# Steering_IOSch.net
KiCad netlist of a schematic drawn in Altium Designer
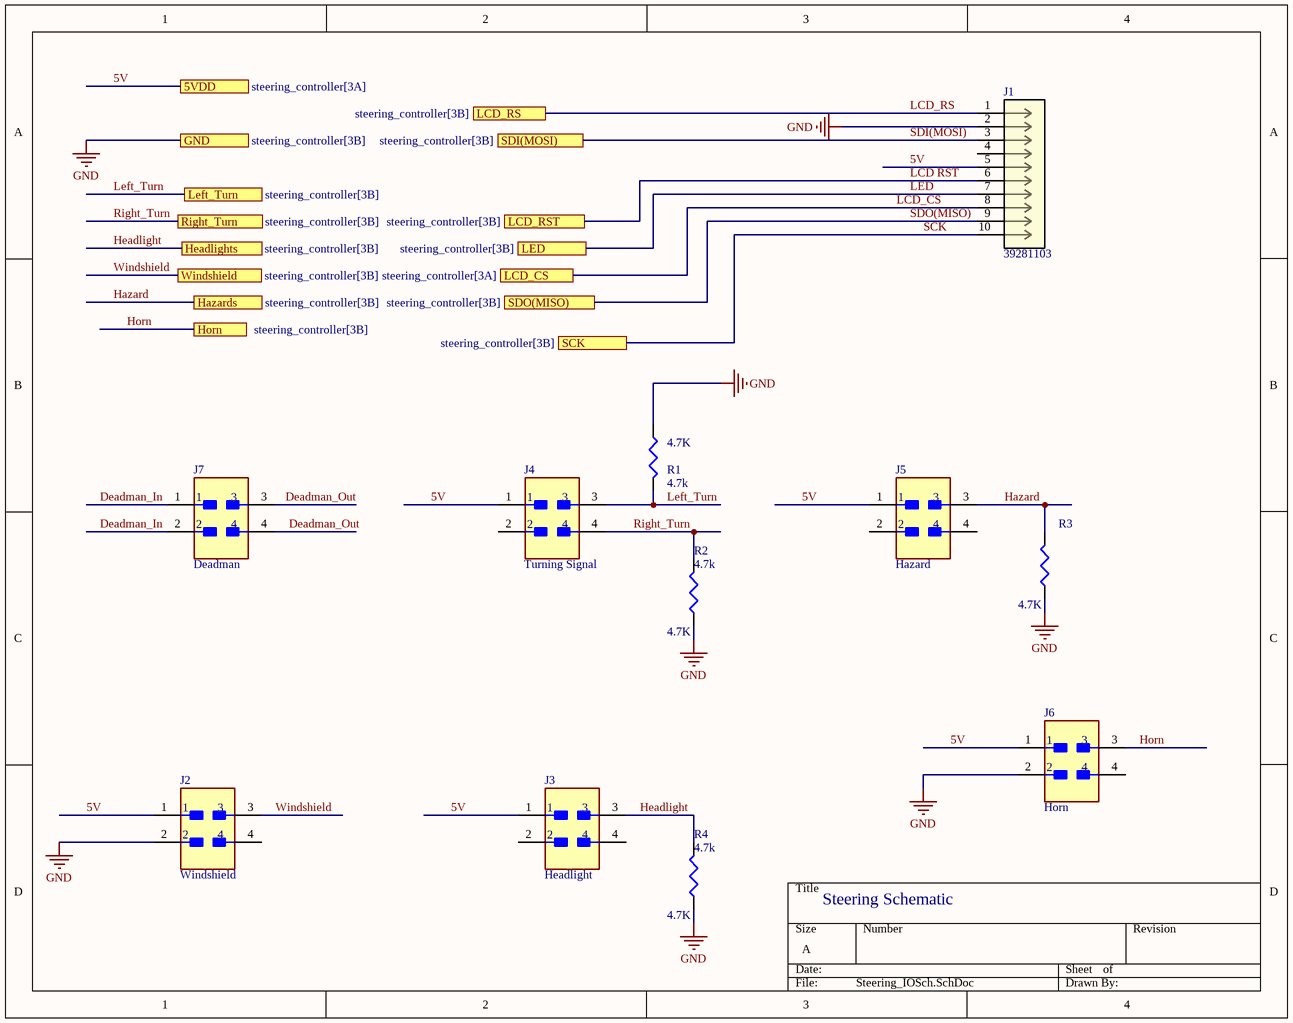
[diagram p0: Steering_IOSch.SchDoc]

(export (version "E")
  (design (tool "Eeschema 10.0.6"))
  (components
    (comp (ref "J1")
      (value "39281103")
      (footprint "CON_39281103")
      (description "No Description Available")
      (libsource (lib "asib") (part "39281103"))
    )
    (comp (ref "J2")
      (value "Windshield")
      (footprint "asib:FP-0039281043-MFG")
      (description "CONN HEADER VERT 4POS 4.2MM. 0039281043")
      (fields (field (name "MANUFACTURER PART NUMBER") "0039281043") (field (name "MANUFACTURER") "Molex"))
      (libsource (lib "asib") (part "1x4_FEMALE_POWER"))
    )
    (comp (ref "J3")
      (value "Headlight")
      (footprint "asib:FP-0039281043-MFG")
      (description "CONN HEADER VERT 4POS 4.2MM. 0039281043")
      (fields (field (name "MANUFACTURER PART NUMBER") "0039281043") (field (name "MANUFACTURER") "Molex"))
      (libsource (lib "asib") (part "1x4_FEMALE_POWER"))
    )
    (comp (ref "J4")
      (value "Turning Signal")
      (footprint "asib:FP-0039281043-MFG")
      (description "CONN HEADER VERT 4POS 4.2MM. 0039281043")
      (fields (field (name "MANUFACTURER PART NUMBER") "0039281043") (field (name "MANUFACTURER") "Molex"))
      (libsource (lib "asib") (part "1x4_FEMALE_POWER"))
    )
    (comp (ref "J5")
      (value "Hazard")
      (footprint "asib:FP-0039281043-MFG")
      (description "CONN HEADER VERT 4POS 4.2MM. 0039281043")
      (fields (field (name "MANUFACTURER PART NUMBER") "0039281043") (field (name "MANUFACTURER") "Molex"))
      (libsource (lib "asib") (part "1x4_FEMALE_POWER"))
    )
    (comp (ref "J6")
      (value "Horn")
      (footprint "asib:FP-0039281043-MFG")
      (description "CONN HEADER VERT 4POS 4.2MM. 0039281043")
      (fields (field (name "MANUFACTURER PART NUMBER") "0039281043") (field (name "MANUFACTURER") "Molex"))
      (libsource (lib "asib") (part "1x4_FEMALE_POWER"))
    )
    (comp (ref "J7")
      (value "Deadman")
      (footprint "asib:FP-0039281043-MFG")
      (description "CONN HEADER VERT 4POS 4.2MM. 0039281043")
      (fields (field (name "MANUFACTURER PART NUMBER") "0039281043") (field (name "MANUFACTURER") "Molex"))
      (libsource (lib "asib") (part "1x4_FEMALE_POWER"))
    )
    (comp (ref "R1")
      (value "4.7k")
      (footprint "0603r")
      (description "SMD Resistor")
      (fields (field (name "ALTIUM_VALUE") "4.7K") (field (name "PUBLISHER") "Altium Limited"))
      (libsource (lib "asib") (part "Res3"))
    )
    (comp (ref "R2")
      (value "4.7k")
      (footprint "0603r")
      (description "SMD Resistor")
      (fields (field (name "ALTIUM_VALUE") "4.7K") (field (name "PUBLISHER") "Altium Limited"))
      (libsource (lib "asib") (part "Res3"))
    )
    (comp (ref "R3")
      (value "4.7K")
      (footprint "0603r")
      (description "SMD Resistor")
      (fields (field (name "PUBLISHER") "Altium Limited"))
      (libsource (lib "asib") (part "Res3"))
    )
    (comp (ref "R4")
      (value "4.7k")
      (footprint "0603r")
      (description "SMD Resistor")
      (fields (field (name "ALTIUM_VALUE") "4.7K") (field (name "PUBLISHER") "Altium Limited"))
      (libsource (lib "asib") (part "Res3"))
    )
  )
  (nets
    (net (code "1") (name "/5V") (class "Default")
      (node (ref "J1") (pin "5") (pinfunction "5_5") (pintype "passive"))
      (node (ref "J2") (pin "1") (pinfunction "1_1") (pintype "passive"))
      (node (ref "J3") (pin "1") (pinfunction "1_1") (pintype "passive"))
      (node (ref "J4") (pin "1") (pinfunction "1_1") (pintype "passive"))
      (node (ref "J5") (pin "1") (pinfunction "1_1") (pintype "passive"))
      (node (ref "J6") (pin "1") (pinfunction "1_1") (pintype "passive"))
    )
    (net (code "2") (name "/Deadman_In") (class "Default")
      (node (ref "J7") (pin "1") (pinfunction "1_1") (pintype "passive"))
      (node (ref "J7") (pin "2") (pinfunction "2_2") (pintype "passive"))
    )
    (net (code "3") (name "/Deadman_Out") (class "Default")
      (node (ref "J7") (pin "3") (pinfunction "3_3") (pintype "passive"))
      (node (ref "J7") (pin "4") (pinfunction "4_4") (pintype "passive"))
    )
    (net (code "4") (name "/Hazard") (class "Default")
      (node (ref "J5") (pin "3") (pinfunction "3_3") (pintype "passive"))
      (node (ref "R3") (pin "2") (pinfunction "2_2") (pintype "passive"))
    )
    (net (code "5") (name "/Headlight") (class "Default")
      (node (ref "J3") (pin "3") (pinfunction "3_3") (pintype "passive"))
      (node (ref "R4") (pin "2") (pinfunction "2_2") (pintype "passive"))
    )
    (net (code "6") (name "/Horn") (class "Default")
      (node (ref "J6") (pin "3") (pinfunction "3_3") (pintype "passive"))
    )
    (net (code "7") (name "/LCD RST") (class "Default")
      (node (ref "J1") (pin "6") (pinfunction "6_6") (pintype "passive"))
    )
    (net (code "8") (name "/LCD_CS") (class "Default")
      (node (ref "J1") (pin "8") (pinfunction "8_8") (pintype "passive"))
    )
    (net (code "9") (name "/LCD_RS") (class "Default")
      (node (ref "J1") (pin "1") (pinfunction "1_1") (pintype "passive"))
    )
    (net (code "10") (name "/LED") (class "Default")
      (node (ref "J1") (pin "7") (pinfunction "7_7") (pintype "passive"))
    )
    (net (code "11") (name "/Left_Turn") (class "Default")
      (node (ref "J4") (pin "3") (pinfunction "3_3") (pintype "passive"))
      (node (ref "R1") (pin "2") (pinfunction "2_2") (pintype "passive"))
    )
    (net (code "12") (name "/Right_Turn") (class "Default")
      (node (ref "J4") (pin "4") (pinfunction "4_4") (pintype "passive"))
      (node (ref "R2") (pin "2") (pinfunction "2_2") (pintype "passive"))
    )
    (net (code "13") (name "/SCK") (class "Default")
      (node (ref "J1") (pin "10") (pinfunction "10_10") (pintype "passive"))
    )
    (net (code "14") (name "/SDI(MOSI)") (class "Default")
      (node (ref "J1") (pin "3") (pinfunction "3_3") (pintype "passive"))
    )
    (net (code "15") (name "/SDO(MISO)") (class "Default")
      (node (ref "J1") (pin "9") (pinfunction "9_9") (pintype "passive"))
    )
    (net (code "16") (name "/Windshield") (class "Default")
      (node (ref "J2") (pin "3") (pinfunction "3_3") (pintype "passive"))
    )
    (net (code "17") (name "GND") (class "Default")
      (node (ref "J1") (pin "2") (pinfunction "2_2") (pintype "passive"))
      (node (ref "J2") (pin "2") (pinfunction "2_2") (pintype "passive"))
      (node (ref "J6") (pin "2") (pinfunction "2_2") (pintype "passive"))
      (node (ref "R1") (pin "1") (pinfunction "1_1") (pintype "passive"))
      (node (ref "R2") (pin "1") (pinfunction "1_1") (pintype "passive"))
      (node (ref "R3") (pin "1") (pinfunction "1_1") (pintype "passive"))
      (node (ref "R4") (pin "1") (pinfunction "1_1") (pintype "passive"))
    )
    (net (code "18") (name "unconnected-(J1-Pad4)") (class "Default")
      (node (ref "J1") (pin "4") (pinfunction "4_4") (pintype "passive"))
    )
    (net (code "19") (name "unconnected-(J2-Pad4)") (class "Default")
      (node (ref "J2") (pin "4") (pinfunction "4_4") (pintype "passive"))
    )
    (net (code "20") (name "unconnected-(J3-Pad2)") (class "Default")
      (node (ref "J3") (pin "2") (pinfunction "2_2") (pintype "passive"))
    )
    (net (code "21") (name "unconnected-(J3-Pad4)") (class "Default")
      (node (ref "J3") (pin "4") (pinfunction "4_4") (pintype "passive"))
    )
    (net (code "22") (name "unconnected-(J4-Pad2)") (class "Default")
      (node (ref "J4") (pin "2") (pinfunction "2_2") (pintype "passive"))
    )
    (net (code "23") (name "unconnected-(J5-Pad2)") (class "Default")
      (node (ref "J5") (pin "2") (pinfunction "2_2") (pintype "passive"))
    )
    (net (code "24") (name "unconnected-(J5-Pad4)") (class "Default")
      (node (ref "J5") (pin "4") (pinfunction "4_4") (pintype "passive"))
    )
    (net (code "25") (name "unconnected-(J6-Pad4)") (class "Default")
      (node (ref "J6") (pin "4") (pinfunction "4_4") (pintype "passive"))
    )
  )
)
